# Skaarhoj_BI8-1x8CAP3slim.net
KiCad netlist of a schematic drawn in EAGLE
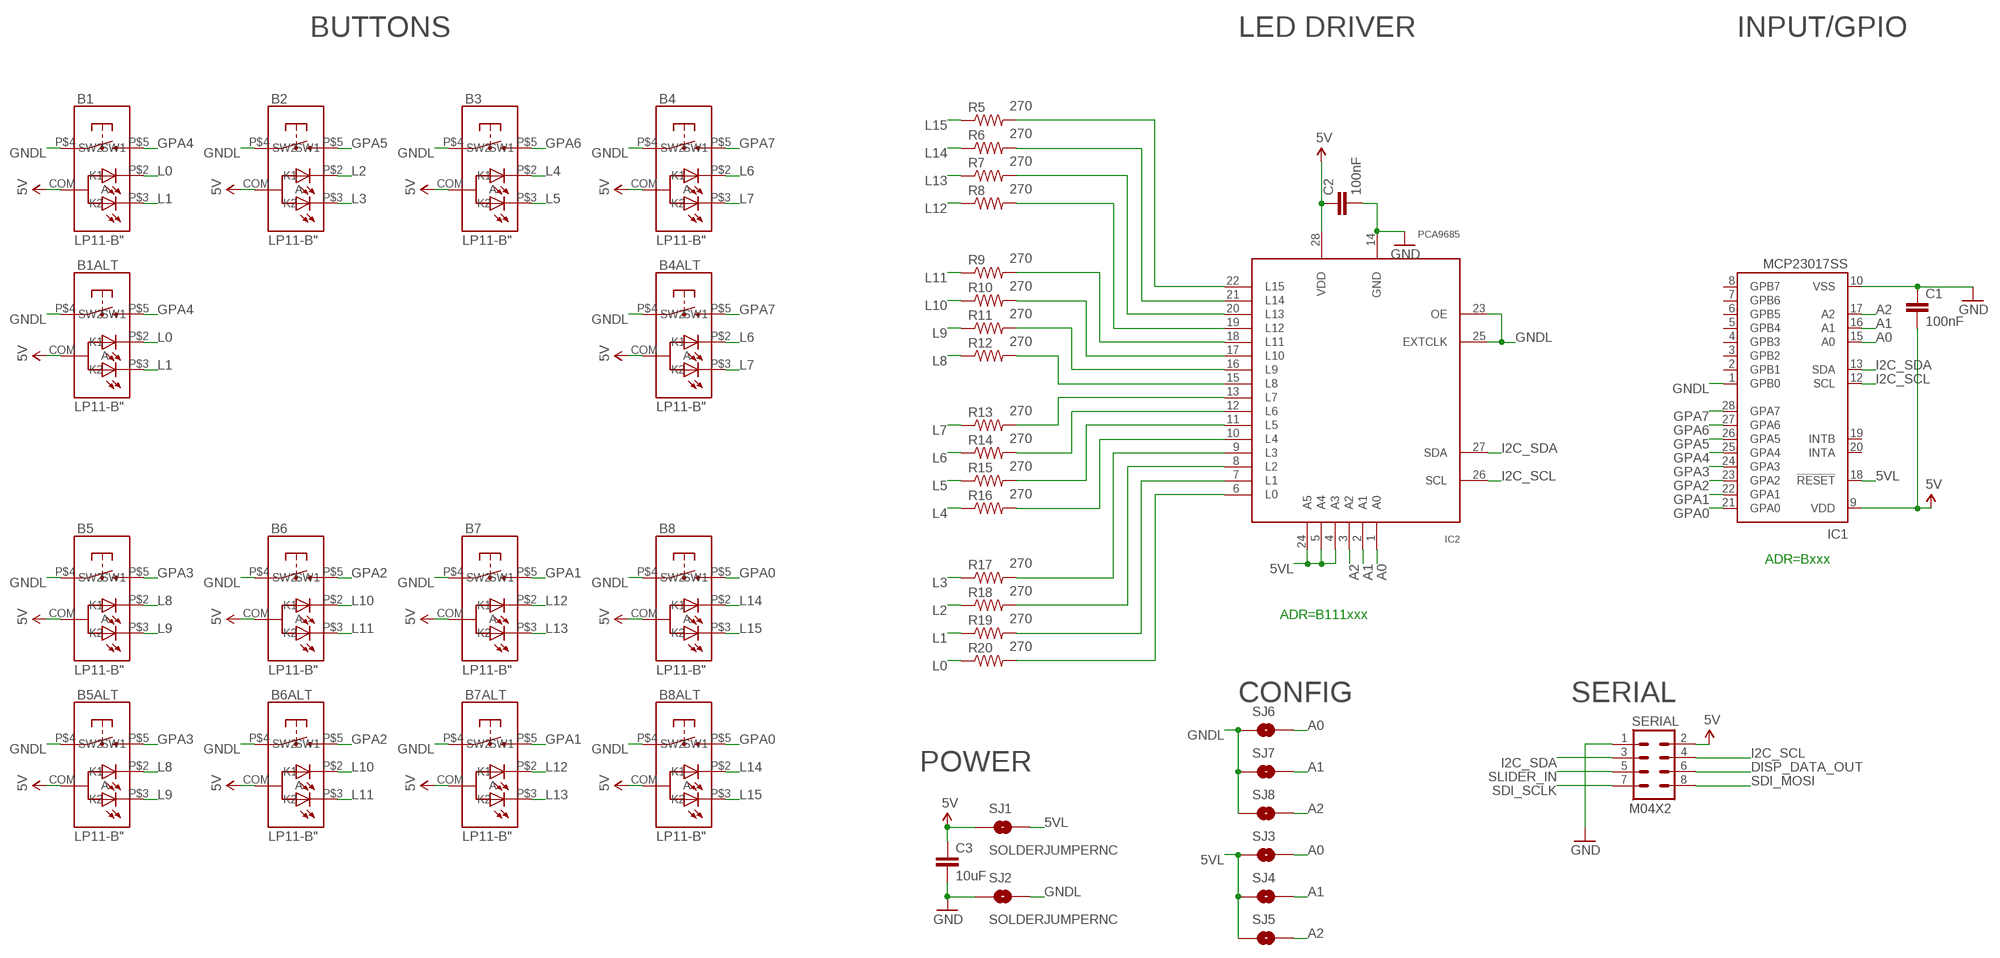
[diagram p0: schematic, sheet 1]

(export (version "E")
  (design (tool "Eeschema 10.0.6"))
  (components
    (comp (ref "B1")
      (value "LP11-B\"")
      (footprint "eagle-import:LP11")
      (libsource (lib "eagle-import") (part "LP11-B{dblquote}"))
    )
    (comp (ref "B1ALT")
      (value "LP11-B\"")
      (footprint "eagle-import:LP11")
      (libsource (lib "eagle-import") (part "LP11-B{dblquote}"))
    )
    (comp (ref "B2")
      (value "LP11-B\"")
      (footprint "eagle-import:LP11")
      (libsource (lib "eagle-import") (part "LP11-B{dblquote}"))
    )
    (comp (ref "B3")
      (value "LP11-B\"")
      (footprint "eagle-import:LP11")
      (libsource (lib "eagle-import") (part "LP11-B{dblquote}"))
    )
    (comp (ref "B4")
      (value "LP11-B\"")
      (footprint "eagle-import:LP11")
      (libsource (lib "eagle-import") (part "LP11-B{dblquote}"))
    )
    (comp (ref "B4ALT")
      (value "LP11-B\"")
      (footprint "eagle-import:LP11")
      (libsource (lib "eagle-import") (part "LP11-B{dblquote}"))
    )
    (comp (ref "B5")
      (value "LP11-B\"")
      (footprint "eagle-import:LP11")
      (libsource (lib "eagle-import") (part "LP11-B{dblquote}"))
    )
    (comp (ref "B5ALT")
      (value "LP11-B\"")
      (footprint "eagle-import:LP11")
      (libsource (lib "eagle-import") (part "LP11-B{dblquote}"))
    )
    (comp (ref "B6")
      (value "LP11-B\"")
      (footprint "eagle-import:LP11")
      (libsource (lib "eagle-import") (part "LP11-B{dblquote}"))
    )
    (comp (ref "B6ALT")
      (value "LP11-B\"")
      (footprint "eagle-import:LP11")
      (libsource (lib "eagle-import") (part "LP11-B{dblquote}"))
    )
    (comp (ref "B7")
      (value "LP11-B\"")
      (footprint "eagle-import:LP11")
      (libsource (lib "eagle-import") (part "LP11-B{dblquote}"))
    )
    (comp (ref "B7ALT")
      (value "LP11-B\"")
      (footprint "eagle-import:LP11")
      (libsource (lib "eagle-import") (part "LP11-B{dblquote}"))
    )
    (comp (ref "B8")
      (value "LP11-B\"")
      (footprint "eagle-import:LP11")
      (libsource (lib "eagle-import") (part "LP11-B{dblquote}"))
    )
    (comp (ref "B8ALT")
      (value "LP11-B\"")
      (footprint "eagle-import:LP11")
      (libsource (lib "eagle-import") (part "LP11-B{dblquote}"))
    )
    (comp (ref "C1")
      (value "100nF")
      (footprint "eagle-import:0603-CAP")
      (libsource (lib "eagle-import") (part "CAP0603-CAP"))
    )
    (comp (ref "C2")
      (value "100nF")
      (footprint "eagle-import:0603-CAP")
      (libsource (lib "eagle-import") (part "CAP0603-CAP"))
    )
    (comp (ref "C3")
      (value "10uF")
      (footprint "eagle-import:0805")
      (libsource (lib "eagle-import") (part "CAP0805"))
    )
    (comp (ref "IC1")
      (value "MCP23017SS")
      (footprint "eagle-import:SSOP28")
      (fields
        (field (name "MF") "MICROCHIP")
        (field (name "MPN") "MCP23017-E/SS")
        (field (name "MPN_1") "MCP23017-E/SS")
        (field (name "OC_FARNELL") "1467674")
        (field (name "OC_NEWARK") "31K2960")
      )
      (libsource (lib "eagle-import") (part "MCP23017SS"))
    )
    (comp (ref "IC2")
      (value "PCA9685")
      (footprint "eagle-import:TSSOP28")
      (libsource (lib "eagle-import") (part "PCA9685"))
    )
    (comp (ref "R5")
      (value "270")
      (footprint "eagle-import:0603-RES")
      (libsource (lib "eagle-import") (part "RESISTOR0603-RES"))
    )
    (comp (ref "R6")
      (value "270")
      (footprint "eagle-import:0603-RES")
      (libsource (lib "eagle-import") (part "RESISTOR0603-RES"))
    )
    (comp (ref "R7")
      (value "270")
      (footprint "eagle-import:0603-RES")
      (libsource (lib "eagle-import") (part "RESISTOR0603-RES"))
    )
    (comp (ref "R8")
      (value "270")
      (footprint "eagle-import:0603-RES")
      (libsource (lib "eagle-import") (part "RESISTOR0603-RES"))
    )
    (comp (ref "R9")
      (value "270")
      (footprint "eagle-import:0603-RES")
      (libsource (lib "eagle-import") (part "RESISTOR0603-RES"))
    )
    (comp (ref "R10")
      (value "270")
      (footprint "eagle-import:0603-RES")
      (libsource (lib "eagle-import") (part "RESISTOR0603-RES"))
    )
    (comp (ref "R11")
      (value "270")
      (footprint "eagle-import:0603-RES")
      (libsource (lib "eagle-import") (part "RESISTOR0603-RES"))
    )
    (comp (ref "R12")
      (value "270")
      (footprint "eagle-import:0603-RES")
      (libsource (lib "eagle-import") (part "RESISTOR0603-RES"))
    )
    (comp (ref "R13")
      (value "270")
      (footprint "eagle-import:0603-RES")
      (libsource (lib "eagle-import") (part "RESISTOR0603-RES"))
    )
    (comp (ref "R14")
      (value "270")
      (footprint "eagle-import:0603-RES")
      (libsource (lib "eagle-import") (part "RESISTOR0603-RES"))
    )
    (comp (ref "R15")
      (value "270")
      (footprint "eagle-import:0603-RES")
      (libsource (lib "eagle-import") (part "RESISTOR0603-RES"))
    )
    (comp (ref "R16")
      (value "270")
      (footprint "eagle-import:0603-RES")
      (libsource (lib "eagle-import") (part "RESISTOR0603-RES"))
    )
    (comp (ref "R17")
      (value "270")
      (footprint "eagle-import:0603-RES")
      (libsource (lib "eagle-import") (part "RESISTOR0603-RES"))
    )
    (comp (ref "R18")
      (value "270")
      (footprint "eagle-import:0603-RES")
      (libsource (lib "eagle-import") (part "RESISTOR0603-RES"))
    )
    (comp (ref "R19")
      (value "270")
      (footprint "eagle-import:0603-RES")
      (libsource (lib "eagle-import") (part "RESISTOR0603-RES"))
    )
    (comp (ref "R20")
      (value "270")
      (footprint "eagle-import:0603-RES")
      (libsource (lib "eagle-import") (part "RESISTOR0603-RES"))
    )
    (comp (ref "SERIAL")
      (value "M04X2")
      (footprint "eagle-import:2X4")
      (libsource (lib "eagle-import") (part "M04X2"))
    )
    (comp (ref "SJ1")
      (value "SOLDERJUMPERNC")
      (footprint "eagle-import:SJ_2S")
      (libsource (lib "eagle-import") (part "SOLDERJUMPERNC"))
    )
    (comp (ref "SJ2")
      (value "SOLDERJUMPERNC")
      (footprint "eagle-import:SJ_2S")
      (libsource (lib "eagle-import") (part "SOLDERJUMPERNC"))
    )
    (comp (ref "SJ3")
      (value "SOLDERJUMPERNC")
      (footprint "eagle-import:SJ_2S")
      (libsource (lib "eagle-import") (part "SOLDERJUMPERNC"))
    )
    (comp (ref "SJ4")
      (value "SOLDERJUMPERNC")
      (footprint "eagle-import:SJ_2S")
      (libsource (lib "eagle-import") (part "SOLDERJUMPERNC"))
    )
    (comp (ref "SJ5")
      (value "SOLDERJUMPERNC")
      (footprint "eagle-import:SJ_2S")
      (libsource (lib "eagle-import") (part "SOLDERJUMPERNC"))
    )
    (comp (ref "SJ6")
      (value "SOLDERJUMPERNC")
      (footprint "eagle-import:SJ_2S")
      (libsource (lib "eagle-import") (part "SOLDERJUMPERNC"))
    )
    (comp (ref "SJ7")
      (value "SOLDERJUMPERNC")
      (footprint "eagle-import:SJ_2S")
      (libsource (lib "eagle-import") (part "SOLDERJUMPERNC"))
    )
    (comp (ref "SJ8")
      (value "SOLDERJUMPERNC")
      (footprint "eagle-import:SJ_2S")
      (libsource (lib "eagle-import") (part "SOLDERJUMPERNC"))
    )
  )
  (nets
    (net (code "1") (name "/5VL") (class "Default")
      (node (ref "IC1") (pin "18") (pinfunction "~{RESET}_18") (pintype "input"))
      (node (ref "IC2") (pin "24") (pinfunction "A5_24") (pintype "input"))
      (node (ref "IC2") (pin "4") (pinfunction "A3_4") (pintype "input"))
      (node (ref "IC2") (pin "5") (pinfunction "A4_5") (pintype "input"))
      (node (ref "SJ1") (pin "2") (pinfunction "2_2") (pintype "passive"))
      (node (ref "SJ3") (pin "1") (pinfunction "1_1") (pintype "passive"))
      (node (ref "SJ4") (pin "1") (pinfunction "1_1") (pintype "passive"))
      (node (ref "SJ5") (pin "1") (pinfunction "1_1") (pintype "passive"))
    )
    (net (code "2") (name "/A0") (class "Default")
      (node (ref "IC1") (pin "15") (pinfunction "A0_15") (pintype "input"))
      (node (ref "IC2") (pin "1") (pinfunction "A0_1") (pintype "input"))
      (node (ref "SJ3") (pin "2") (pinfunction "2_2") (pintype "passive"))
      (node (ref "SJ6") (pin "2") (pinfunction "2_2") (pintype "passive"))
    )
    (net (code "3") (name "/A1") (class "Default")
      (node (ref "IC1") (pin "16") (pinfunction "A1_16") (pintype "input"))
      (node (ref "IC2") (pin "2") (pinfunction "A1_2") (pintype "input"))
      (node (ref "SJ4") (pin "2") (pinfunction "2_2") (pintype "passive"))
      (node (ref "SJ7") (pin "2") (pinfunction "2_2") (pintype "passive"))
    )
    (net (code "4") (name "/A2") (class "Default")
      (node (ref "IC1") (pin "17") (pinfunction "A2_17") (pintype "input"))
      (node (ref "IC2") (pin "3") (pinfunction "A2_3") (pintype "input"))
      (node (ref "SJ5") (pin "2") (pinfunction "2_2") (pintype "passive"))
      (node (ref "SJ8") (pin "2") (pinfunction "2_2") (pintype "passive"))
    )
    (net (code "5") (name "/DISP_DATA_OUT") (class "Default")
      (node (ref "SERIAL") (pin "6") (pinfunction "6_6") (pintype "passive"))
    )
    (net (code "6") (name "/GNDL") (class "Default")
      (node (ref "B1") (pin "P$4") (pinfunction "SW1_P$4") (pintype "bidirectional"))
      (node (ref "B1ALT") (pin "P$4") (pinfunction "SW1_P$4") (pintype "bidirectional"))
      (node (ref "B2") (pin "P$4") (pinfunction "SW1_P$4") (pintype "bidirectional"))
      (node (ref "B3") (pin "P$4") (pinfunction "SW1_P$4") (pintype "bidirectional"))
      (node (ref "B4") (pin "P$4") (pinfunction "SW1_P$4") (pintype "bidirectional"))
      (node (ref "B4ALT") (pin "P$4") (pinfunction "SW1_P$4") (pintype "bidirectional"))
      (node (ref "B5") (pin "P$4") (pinfunction "SW1_P$4") (pintype "bidirectional"))
      (node (ref "B5ALT") (pin "P$4") (pinfunction "SW1_P$4") (pintype "bidirectional"))
      (node (ref "B6") (pin "P$4") (pinfunction "SW1_P$4") (pintype "bidirectional"))
      (node (ref "B6ALT") (pin "P$4") (pinfunction "SW1_P$4") (pintype "bidirectional"))
      (node (ref "B7") (pin "P$4") (pinfunction "SW1_P$4") (pintype "bidirectional"))
      (node (ref "B7ALT") (pin "P$4") (pinfunction "SW1_P$4") (pintype "bidirectional"))
      (node (ref "B8") (pin "P$4") (pinfunction "SW1_P$4") (pintype "bidirectional"))
      (node (ref "B8ALT") (pin "P$4") (pinfunction "SW1_P$4") (pintype "bidirectional"))
      (node (ref "IC1") (pin "1") (pinfunction "GPB0_1") (pintype "bidirectional"))
      (node (ref "IC2") (pin "23") (pinfunction "OE_23") (pintype "input"))
      (node (ref "IC2") (pin "25") (pinfunction "EXTCLK_25") (pintype "input"))
      (node (ref "SJ2") (pin "2") (pinfunction "2_2") (pintype "passive"))
      (node (ref "SJ6") (pin "1") (pinfunction "1_1") (pintype "passive"))
      (node (ref "SJ7") (pin "1") (pinfunction "1_1") (pintype "passive"))
      (node (ref "SJ8") (pin "1") (pinfunction "1_1") (pintype "passive"))
    )
    (net (code "7") (name "/GPA0") (class "Default")
      (node (ref "B8") (pin "P$5") (pinfunction "SW2_P$5") (pintype "bidirectional"))
      (node (ref "B8ALT") (pin "P$5") (pinfunction "SW2_P$5") (pintype "bidirectional"))
      (node (ref "IC1") (pin "21") (pinfunction "GPA0_21") (pintype "bidirectional"))
    )
    (net (code "8") (name "/GPA1") (class "Default")
      (node (ref "B7") (pin "P$5") (pinfunction "SW2_P$5") (pintype "bidirectional"))
      (node (ref "B7ALT") (pin "P$5") (pinfunction "SW2_P$5") (pintype "bidirectional"))
      (node (ref "IC1") (pin "22") (pinfunction "GPA1_22") (pintype "bidirectional"))
    )
    (net (code "9") (name "/GPA2") (class "Default")
      (node (ref "B6") (pin "P$5") (pinfunction "SW2_P$5") (pintype "bidirectional"))
      (node (ref "B6ALT") (pin "P$5") (pinfunction "SW2_P$5") (pintype "bidirectional"))
      (node (ref "IC1") (pin "23") (pinfunction "GPA2_23") (pintype "bidirectional"))
    )
    (net (code "10") (name "/GPA3") (class "Default")
      (node (ref "B5") (pin "P$5") (pinfunction "SW2_P$5") (pintype "bidirectional"))
      (node (ref "B5ALT") (pin "P$5") (pinfunction "SW2_P$5") (pintype "bidirectional"))
      (node (ref "IC1") (pin "24") (pinfunction "GPA3_24") (pintype "bidirectional"))
    )
    (net (code "11") (name "/GPA4") (class "Default")
      (node (ref "B1") (pin "P$5") (pinfunction "SW2_P$5") (pintype "bidirectional"))
      (node (ref "B1ALT") (pin "P$5") (pinfunction "SW2_P$5") (pintype "bidirectional"))
      (node (ref "IC1") (pin "25") (pinfunction "GPA4_25") (pintype "bidirectional"))
    )
    (net (code "12") (name "/GPA5") (class "Default")
      (node (ref "B2") (pin "P$5") (pinfunction "SW2_P$5") (pintype "bidirectional"))
      (node (ref "IC1") (pin "26") (pinfunction "GPA5_26") (pintype "bidirectional"))
    )
    (net (code "13") (name "/GPA6") (class "Default")
      (node (ref "B3") (pin "P$5") (pinfunction "SW2_P$5") (pintype "bidirectional"))
      (node (ref "IC1") (pin "27") (pinfunction "GPA6_27") (pintype "bidirectional"))
    )
    (net (code "14") (name "/GPA7") (class "Default")
      (node (ref "B4") (pin "P$5") (pinfunction "SW2_P$5") (pintype "bidirectional"))
      (node (ref "B4ALT") (pin "P$5") (pinfunction "SW2_P$5") (pintype "bidirectional"))
      (node (ref "IC1") (pin "28") (pinfunction "GPA7_28") (pintype "bidirectional"))
    )
    (net (code "15") (name "/I2C_SCL") (class "Default")
      (node (ref "IC1") (pin "12") (pinfunction "SCL_12") (pintype "input"))
      (node (ref "IC2") (pin "26") (pinfunction "SCL_26") (pintype "input"))
      (node (ref "SERIAL") (pin "4") (pinfunction "4_4") (pintype "passive"))
    )
    (net (code "16") (name "/I2C_SDA") (class "Default")
      (node (ref "IC1") (pin "13") (pinfunction "SDA_13") (pintype "bidirectional"))
      (node (ref "IC2") (pin "27") (pinfunction "SDA_27") (pintype "input"))
      (node (ref "SERIAL") (pin "3") (pinfunction "3_3") (pintype "passive"))
    )
    (net (code "17") (name "/L0") (class "Default")
      (node (ref "B1") (pin "P$2") (pinfunction "K1_P$2") (pintype "bidirectional"))
      (node (ref "B1ALT") (pin "P$2") (pinfunction "K1_P$2") (pintype "bidirectional"))
      (node (ref "R20") (pin "1") (pinfunction "1_1") (pintype "passive"))
    )
    (net (code "18") (name "/L1") (class "Default")
      (node (ref "B1") (pin "P$3") (pinfunction "K2_P$3") (pintype "bidirectional"))
      (node (ref "B1ALT") (pin "P$3") (pinfunction "K2_P$3") (pintype "bidirectional"))
      (node (ref "R19") (pin "1") (pinfunction "1_1") (pintype "passive"))
    )
    (net (code "19") (name "/L2") (class "Default")
      (node (ref "B2") (pin "P$2") (pinfunction "K1_P$2") (pintype "bidirectional"))
      (node (ref "R18") (pin "1") (pinfunction "1_1") (pintype "passive"))
    )
    (net (code "20") (name "/L3") (class "Default")
      (node (ref "B2") (pin "P$3") (pinfunction "K2_P$3") (pintype "bidirectional"))
      (node (ref "R17") (pin "1") (pinfunction "1_1") (pintype "passive"))
    )
    (net (code "21") (name "/L4") (class "Default")
      (node (ref "B3") (pin "P$2") (pinfunction "K1_P$2") (pintype "bidirectional"))
      (node (ref "R16") (pin "1") (pinfunction "1_1") (pintype "passive"))
    )
    (net (code "22") (name "/L5") (class "Default")
      (node (ref "B3") (pin "P$3") (pinfunction "K2_P$3") (pintype "bidirectional"))
      (node (ref "R15") (pin "1") (pinfunction "1_1") (pintype "passive"))
    )
    (net (code "23") (name "/L6") (class "Default")
      (node (ref "B4") (pin "P$2") (pinfunction "K1_P$2") (pintype "bidirectional"))
      (node (ref "B4ALT") (pin "P$2") (pinfunction "K1_P$2") (pintype "bidirectional"))
      (node (ref "R14") (pin "1") (pinfunction "1_1") (pintype "passive"))
    )
    (net (code "24") (name "/L7") (class "Default")
      (node (ref "B4") (pin "P$3") (pinfunction "K2_P$3") (pintype "bidirectional"))
      (node (ref "B4ALT") (pin "P$3") (pinfunction "K2_P$3") (pintype "bidirectional"))
      (node (ref "R13") (pin "1") (pinfunction "1_1") (pintype "passive"))
    )
    (net (code "25") (name "/L8") (class "Default")
      (node (ref "B5") (pin "P$2") (pinfunction "K1_P$2") (pintype "bidirectional"))
      (node (ref "B5ALT") (pin "P$2") (pinfunction "K1_P$2") (pintype "bidirectional"))
      (node (ref "R12") (pin "1") (pinfunction "1_1") (pintype "passive"))
    )
    (net (code "26") (name "/L9") (class "Default")
      (node (ref "B5") (pin "P$3") (pinfunction "K2_P$3") (pintype "bidirectional"))
      (node (ref "B5ALT") (pin "P$3") (pinfunction "K2_P$3") (pintype "bidirectional"))
      (node (ref "R11") (pin "1") (pinfunction "1_1") (pintype "passive"))
    )
    (net (code "27") (name "/L10") (class "Default")
      (node (ref "B6") (pin "P$2") (pinfunction "K1_P$2") (pintype "bidirectional"))
      (node (ref "B6ALT") (pin "P$2") (pinfunction "K1_P$2") (pintype "bidirectional"))
      (node (ref "R10") (pin "1") (pinfunction "1_1") (pintype "passive"))
    )
    (net (code "28") (name "/L11") (class "Default")
      (node (ref "B6") (pin "P$3") (pinfunction "K2_P$3") (pintype "bidirectional"))
      (node (ref "B6ALT") (pin "P$3") (pinfunction "K2_P$3") (pintype "bidirectional"))
      (node (ref "R9") (pin "1") (pinfunction "1_1") (pintype "passive"))
    )
    (net (code "29") (name "/L12") (class "Default")
      (node (ref "B7") (pin "P$2") (pinfunction "K1_P$2") (pintype "bidirectional"))
      (node (ref "B7ALT") (pin "P$2") (pinfunction "K1_P$2") (pintype "bidirectional"))
      (node (ref "R8") (pin "1") (pinfunction "1_1") (pintype "passive"))
    )
    (net (code "30") (name "/L13") (class "Default")
      (node (ref "B7") (pin "P$3") (pinfunction "K2_P$3") (pintype "bidirectional"))
      (node (ref "B7ALT") (pin "P$3") (pinfunction "K2_P$3") (pintype "bidirectional"))
      (node (ref "R7") (pin "1") (pinfunction "1_1") (pintype "passive"))
    )
    (net (code "31") (name "/L14") (class "Default")
      (node (ref "B8") (pin "P$2") (pinfunction "K1_P$2") (pintype "bidirectional"))
      (node (ref "B8ALT") (pin "P$2") (pinfunction "K1_P$2") (pintype "bidirectional"))
      (node (ref "R6") (pin "1") (pinfunction "1_1") (pintype "passive"))
    )
    (net (code "32") (name "/L15") (class "Default")
      (node (ref "B8") (pin "P$3") (pinfunction "K2_P$3") (pintype "bidirectional"))
      (node (ref "B8ALT") (pin "P$3") (pinfunction "K2_P$3") (pintype "bidirectional"))
      (node (ref "R5") (pin "1") (pinfunction "1_1") (pintype "passive"))
    )
    (net (code "33") (name "/SDI_MOSI") (class "Default")
      (node (ref "SERIAL") (pin "8") (pinfunction "8_8") (pintype "passive"))
    )
    (net (code "34") (name "/SDI_SCLK") (class "Default")
      (node (ref "SERIAL") (pin "7") (pinfunction "7_7") (pintype "passive"))
    )
    (net (code "35") (name "/SLIDER_IN") (class "Default")
      (node (ref "SERIAL") (pin "5") (pinfunction "5_5") (pintype "passive"))
    )
    (net (code "36") (name "5V") (class "Default")
      (node (ref "B1") (pin "COM") (pinfunction "A_COM") (pintype "bidirectional"))
      (node (ref "B1ALT") (pin "COM") (pinfunction "A_COM") (pintype "bidirectional"))
      (node (ref "B2") (pin "COM") (pinfunction "A_COM") (pintype "bidirectional"))
      (node (ref "B3") (pin "COM") (pinfunction "A_COM") (pintype "bidirectional"))
      (node (ref "B4") (pin "COM") (pinfunction "A_COM") (pintype "bidirectional"))
      (node (ref "B4ALT") (pin "COM") (pinfunction "A_COM") (pintype "bidirectional"))
      (node (ref "B5") (pin "COM") (pinfunction "A_COM") (pintype "bidirectional"))
      (node (ref "B5ALT") (pin "COM") (pinfunction "A_COM") (pintype "bidirectional"))
      (node (ref "B6") (pin "COM") (pinfunction "A_COM") (pintype "bidirectional"))
      (node (ref "B6ALT") (pin "COM") (pinfunction "A_COM") (pintype "bidirectional"))
      (node (ref "B7") (pin "COM") (pinfunction "A_COM") (pintype "bidirectional"))
      (node (ref "B7ALT") (pin "COM") (pinfunction "A_COM") (pintype "bidirectional"))
      (node (ref "B8") (pin "COM") (pinfunction "A_COM") (pintype "bidirectional"))
      (node (ref "B8ALT") (pin "COM") (pinfunction "A_COM") (pintype "bidirectional"))
      (node (ref "C1") (pin "2") (pinfunction "2_2") (pintype "passive"))
      (node (ref "C2") (pin "1") (pinfunction "1_1") (pintype "passive"))
      (node (ref "C3") (pin "1") (pinfunction "1_1") (pintype "passive"))
      (node (ref "IC1") (pin "9") (pinfunction "VDD_9") (pintype "power_in"))
      (node (ref "IC2") (pin "28") (pinfunction "VDD_28") (pintype "power_in"))
      (node (ref "SERIAL") (pin "2") (pinfunction "2_2") (pintype "passive"))
      (node (ref "SJ1") (pin "1") (pinfunction "1_1") (pintype "passive"))
    )
    (net (code "37") (name "GND") (class "Default")
      (node (ref "C1") (pin "1") (pinfunction "1_1") (pintype "passive"))
      (node (ref "C2") (pin "2") (pinfunction "2_2") (pintype "passive"))
      (node (ref "C3") (pin "2") (pinfunction "2_2") (pintype "passive"))
      (node (ref "IC1") (pin "10") (pinfunction "VSS_10") (pintype "power_in"))
      (node (ref "IC2") (pin "14") (pinfunction "GND_14") (pintype "power_in"))
      (node (ref "SERIAL") (pin "1") (pinfunction "1_1") (pintype "passive"))
      (node (ref "SJ2") (pin "1") (pinfunction "1_1") (pintype "passive"))
    )
    (net (code "38") (name "Net-(IC2-L0)") (class "Default")
      (node (ref "IC2") (pin "6") (pinfunction "L0_6") (pintype "output"))
      (node (ref "R20") (pin "2") (pinfunction "2_2") (pintype "passive"))
    )
    (net (code "39") (name "Net-(IC2-L1)") (class "Default")
      (node (ref "IC2") (pin "7") (pinfunction "L1_7") (pintype "output"))
      (node (ref "R19") (pin "2") (pinfunction "2_2") (pintype "passive"))
    )
    (net (code "40") (name "Net-(IC2-L2)") (class "Default")
      (node (ref "IC2") (pin "8") (pinfunction "L2_8") (pintype "output"))
      (node (ref "R18") (pin "2") (pinfunction "2_2") (pintype "passive"))
    )
    (net (code "41") (name "Net-(IC2-L3)") (class "Default")
      (node (ref "IC2") (pin "9") (pinfunction "L3_9") (pintype "output"))
      (node (ref "R17") (pin "2") (pinfunction "2_2") (pintype "passive"))
    )
    (net (code "42") (name "Net-(IC2-L4)") (class "Default")
      (node (ref "IC2") (pin "10") (pinfunction "L4_10") (pintype "output"))
      (node (ref "R16") (pin "2") (pinfunction "2_2") (pintype "passive"))
    )
    (net (code "43") (name "Net-(IC2-L5)") (class "Default")
      (node (ref "IC2") (pin "11") (pinfunction "L5_11") (pintype "output"))
      (node (ref "R15") (pin "2") (pinfunction "2_2") (pintype "passive"))
    )
    (net (code "44") (name "Net-(IC2-L6)") (class "Default")
      (node (ref "IC2") (pin "12") (pinfunction "L6_12") (pintype "output"))
      (node (ref "R14") (pin "2") (pinfunction "2_2") (pintype "passive"))
    )
    (net (code "45") (name "Net-(IC2-L7)") (class "Default")
      (node (ref "IC2") (pin "13") (pinfunction "L7_13") (pintype "output"))
      (node (ref "R13") (pin "2") (pinfunction "2_2") (pintype "passive"))
    )
    (net (code "46") (name "Net-(IC2-L8)") (class "Default")
      (node (ref "IC2") (pin "15") (pinfunction "L8_15") (pintype "output"))
      (node (ref "R12") (pin "2") (pinfunction "2_2") (pintype "passive"))
    )
    (net (code "47") (name "Net-(IC2-L9)") (class "Default")
      (node (ref "IC2") (pin "16") (pinfunction "L9_16") (pintype "output"))
      (node (ref "R11") (pin "2") (pinfunction "2_2") (pintype "passive"))
    )
    (net (code "48") (name "Net-(IC2-L10)") (class "Default")
      (node (ref "IC2") (pin "17") (pinfunction "L10_17") (pintype "output"))
      (node (ref "R10") (pin "2") (pinfunction "2_2") (pintype "passive"))
    )
    (net (code "49") (name "Net-(IC2-L11)") (class "Default")
      (node (ref "IC2") (pin "18") (pinfunction "L11_18") (pintype "output"))
      (node (ref "R9") (pin "2") (pinfunction "2_2") (pintype "passive"))
    )
    (net (code "50") (name "Net-(IC2-L12)") (class "Default")
      (node (ref "IC2") (pin "19") (pinfunction "L12_19") (pintype "output"))
      (node (ref "R8") (pin "2") (pinfunction "2_2") (pintype "passive"))
    )
    (net (code "51") (name "Net-(IC2-L13)") (class "Default")
      (node (ref "IC2") (pin "20") (pinfunction "L13_20") (pintype "output"))
      (node (ref "R7") (pin "2") (pinfunction "2_2") (pintype "passive"))
    )
    (net (code "52") (name "Net-(IC2-L14)") (class "Default")
      (node (ref "IC2") (pin "21") (pinfunction "L14_21") (pintype "output"))
      (node (ref "R6") (pin "2") (pinfunction "2_2") (pintype "passive"))
    )
    (net (code "53") (name "Net-(IC2-L15)") (class "Default")
      (node (ref "IC2") (pin "22") (pinfunction "L15_22") (pintype "output"))
      (node (ref "R5") (pin "2") (pinfunction "2_2") (pintype "passive"))
    )
    (net (code "54") (name "unconnected-(IC1-GPB1-Pad2)") (class "Default")
      (node (ref "IC1") (pin "2") (pinfunction "GPB1_2") (pintype "bidirectional"))
    )
    (net (code "55") (name "unconnected-(IC1-GPB2-Pad3)") (class "Default")
      (node (ref "IC1") (pin "3") (pinfunction "GPB2_3") (pintype "bidirectional"))
    )
    (net (code "56") (name "unconnected-(IC1-GPB3-Pad4)") (class "Default")
      (node (ref "IC1") (pin "4") (pinfunction "GPB3_4") (pintype "bidirectional"))
    )
    (net (code "57") (name "unconnected-(IC1-GPB4-Pad5)") (class "Default")
      (node (ref "IC1") (pin "5") (pinfunction "GPB4_5") (pintype "bidirectional"))
    )
    (net (code "58") (name "unconnected-(IC1-GPB5-Pad6)") (class "Default")
      (node (ref "IC1") (pin "6") (pinfunction "GPB5_6") (pintype "bidirectional"))
    )
    (net (code "59") (name "unconnected-(IC1-GPB6-Pad7)") (class "Default")
      (node (ref "IC1") (pin "7") (pinfunction "GPB6_7") (pintype "bidirectional"))
    )
    (net (code "60") (name "unconnected-(IC1-GPB7-Pad8)") (class "Default")
      (node (ref "IC1") (pin "8") (pinfunction "GPB7_8") (pintype "bidirectional"))
    )
    (net (code "61") (name "unconnected-(IC1-INTA-Pad20)") (class "Default")
      (node (ref "IC1") (pin "20") (pinfunction "INTA_20") (pintype "output"))
    )
    (net (code "62") (name "unconnected-(IC1-INTB-Pad19)") (class "Default")
      (node (ref "IC1") (pin "19") (pinfunction "INTB_19") (pintype "output"))
    )
  )
)
